# Octaverter_Rev_5.net
KiCad netlist of a schematic drawn in EAGLE
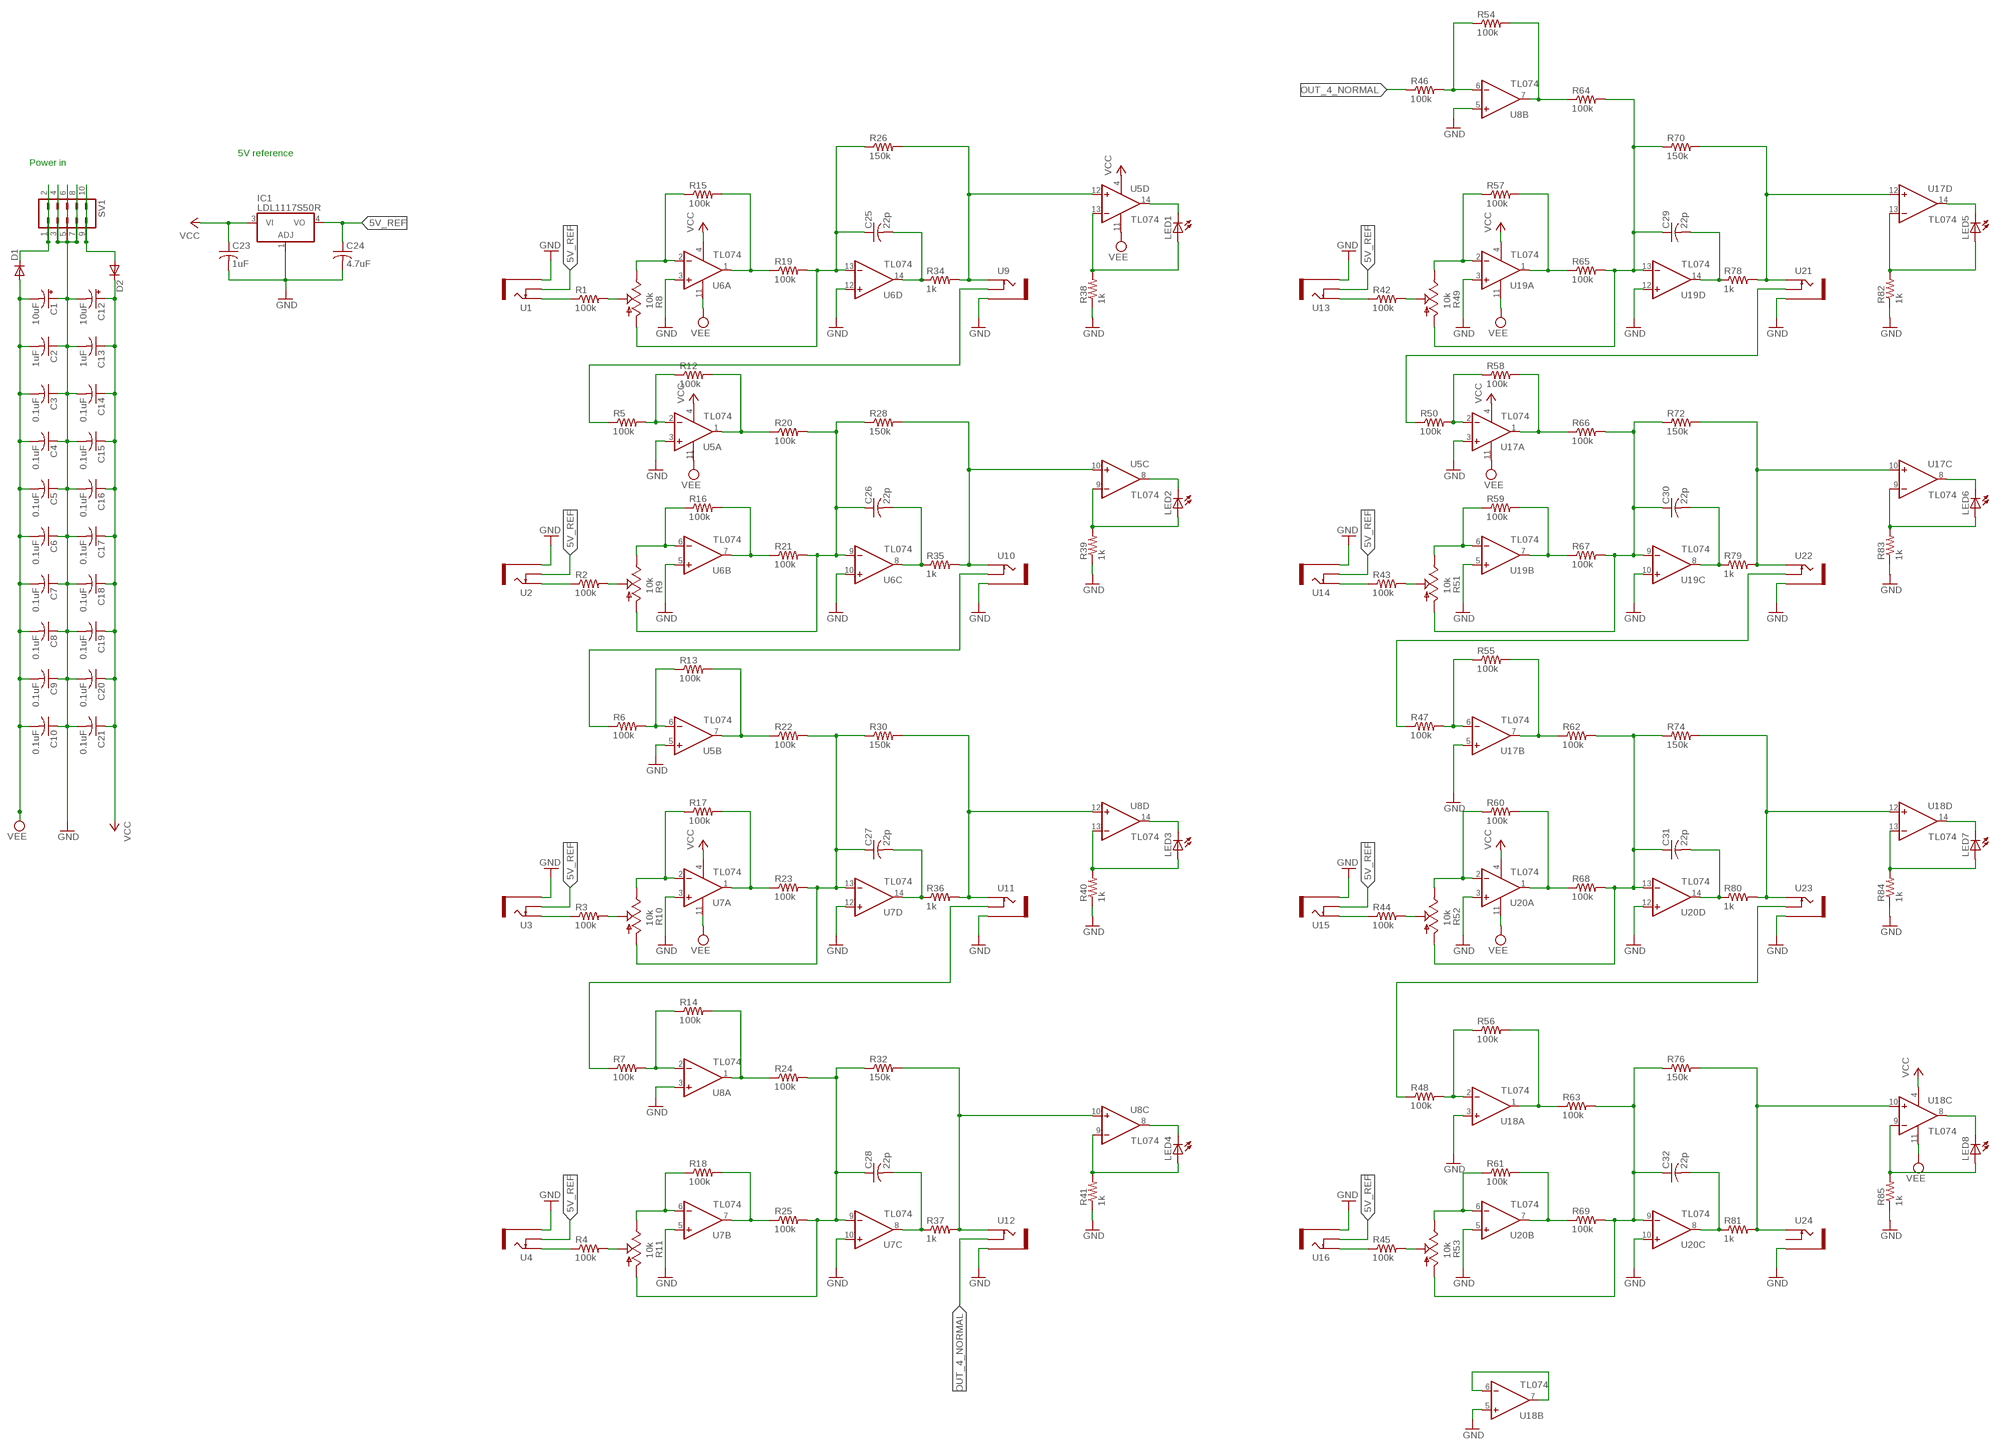
[diagram p0: schematic, sheet 1]

(export (version "E")
  (design (tool "Eeschema 10.0.6"))
  (components
    (comp (ref "C1")
      (value "10uF")
      (footprint "eagle-import:PANASONIC_B")
      (libsource (lib "eagle-import") (part "CPOL-USB"))
    )
    (comp (ref "C2")
      (value "1uF")
      (footprint "eagle-import:C0603")
      (libsource (lib "eagle-import") (part "C-USC0603"))
    )
    (comp (ref "C3")
      (value "0.1uF")
      (footprint "eagle-import:C0603")
      (libsource (lib "eagle-import") (part "C-USC0603"))
    )
    (comp (ref "C4")
      (value "0.1uF")
      (footprint "eagle-import:C0603")
      (libsource (lib "eagle-import") (part "C-USC0603"))
    )
    (comp (ref "C5")
      (value "0.1uF")
      (footprint "eagle-import:C0603")
      (libsource (lib "eagle-import") (part "C-USC0603"))
    )
    (comp (ref "C6")
      (value "0.1uF")
      (footprint "eagle-import:C0603")
      (libsource (lib "eagle-import") (part "C-USC0603"))
    )
    (comp (ref "C7")
      (value "0.1uF")
      (footprint "eagle-import:C0603")
      (libsource (lib "eagle-import") (part "C-USC0603"))
    )
    (comp (ref "C8")
      (value "0.1uF")
      (footprint "eagle-import:C0603")
      (libsource (lib "eagle-import") (part "C-USC0603"))
    )
    (comp (ref "C9")
      (value "0.1uF")
      (footprint "eagle-import:C0603")
      (libsource (lib "eagle-import") (part "C-USC0603"))
    )
    (comp (ref "C10")
      (value "0.1uF")
      (footprint "eagle-import:C0603")
      (libsource (lib "eagle-import") (part "C-USC0603"))
    )
    (comp (ref "C12")
      (value "10uF")
      (footprint "eagle-import:PANASONIC_B")
      (libsource (lib "eagle-import") (part "CPOL-USB"))
    )
    (comp (ref "C13")
      (value "1uF")
      (footprint "eagle-import:C0603")
      (libsource (lib "eagle-import") (part "C-USC0603"))
    )
    (comp (ref "C14")
      (value "0.1uF")
      (footprint "eagle-import:C0603")
      (libsource (lib "eagle-import") (part "C-USC0603"))
    )
    (comp (ref "C15")
      (value "0.1uF")
      (footprint "eagle-import:C0603")
      (libsource (lib "eagle-import") (part "C-USC0603"))
    )
    (comp (ref "C16")
      (value "0.1uF")
      (footprint "eagle-import:C0603")
      (libsource (lib "eagle-import") (part "C-USC0603"))
    )
    (comp (ref "C17")
      (value "0.1uF")
      (footprint "eagle-import:C0603")
      (libsource (lib "eagle-import") (part "C-USC0603"))
    )
    (comp (ref "C18")
      (value "0.1uF")
      (footprint "eagle-import:C0603")
      (libsource (lib "eagle-import") (part "C-USC0603"))
    )
    (comp (ref "C19")
      (value "0.1uF")
      (footprint "eagle-import:C0603")
      (libsource (lib "eagle-import") (part "C-USC0603"))
    )
    (comp (ref "C20")
      (value "0.1uF")
      (footprint "eagle-import:C0603")
      (libsource (lib "eagle-import") (part "C-USC0603"))
    )
    (comp (ref "C21")
      (value "0.1uF")
      (footprint "eagle-import:C0603")
      (libsource (lib "eagle-import") (part "C-USC0603"))
    )
    (comp (ref "C23")
      (value "1uF")
      (footprint "eagle-import:C0603")
      (libsource (lib "eagle-import") (part "C-USC0603"))
    )
    (comp (ref "C24")
      (value "4.7uF")
      (footprint "eagle-import:C0603")
      (libsource (lib "eagle-import") (part "C-USC0603"))
    )
    (comp (ref "C25")
      (value "22p")
      (footprint "eagle-import:C0603")
      (libsource (lib "eagle-import") (part "C-USC0603"))
    )
    (comp (ref "C26")
      (value "22p")
      (footprint "eagle-import:C0603")
      (libsource (lib "eagle-import") (part "C-USC0603"))
    )
    (comp (ref "C27")
      (value "22p")
      (footprint "eagle-import:C0603")
      (libsource (lib "eagle-import") (part "C-USC0603"))
    )
    (comp (ref "C28")
      (value "22p")
      (footprint "eagle-import:C0603")
      (libsource (lib "eagle-import") (part "C-USC0603"))
    )
    (comp (ref "C29")
      (value "22p")
      (footprint "eagle-import:C0603")
      (libsource (lib "eagle-import") (part "C-USC0603"))
    )
    (comp (ref "C30")
      (value "22p")
      (footprint "eagle-import:C0603")
      (libsource (lib "eagle-import") (part "C-USC0603"))
    )
    (comp (ref "C31")
      (value "22p")
      (footprint "eagle-import:C0603")
      (libsource (lib "eagle-import") (part "C-USC0603"))
    )
    (comp (ref "C32")
      (value "22p")
      (footprint "eagle-import:C0603")
      (libsource (lib "eagle-import") (part "C-USC0603"))
    )
    (comp (ref "D1")
      (value "1N5819HW")
      (footprint "eagle-import:SOD123")
      (libsource (lib "eagle-import") (part "DIODE-SOD123"))
    )
    (comp (ref "D2")
      (value "1N5819HW")
      (footprint "eagle-import:SOD123")
      (libsource (lib "eagle-import") (part "DIODE-SOD123"))
    )
    (comp (ref "IC1")
      (value "LDL1117S50R")
      (footprint "eagle-import:SOT223")
      (libsource (lib "eagle-import") (part "317EMP"))
    )
    (comp (ref "LED1")
      (value "LED3MM")
      (footprint "eagle-import:LED3MM")
      (libsource (lib "eagle-import") (part "LED3MM"))
    )
    (comp (ref "LED2")
      (value "LED3MM")
      (footprint "eagle-import:LED3MM")
      (libsource (lib "eagle-import") (part "LED3MM"))
    )
    (comp (ref "LED3")
      (value "LED3MM")
      (footprint "eagle-import:LED3MM")
      (libsource (lib "eagle-import") (part "LED3MM"))
    )
    (comp (ref "LED4")
      (value "LED3MM")
      (footprint "eagle-import:LED3MM")
      (libsource (lib "eagle-import") (part "LED3MM"))
    )
    (comp (ref "LED5")
      (value "LED3MM")
      (footprint "eagle-import:LED3MM")
      (libsource (lib "eagle-import") (part "LED3MM"))
    )
    (comp (ref "LED6")
      (value "LED3MM")
      (footprint "eagle-import:LED3MM")
      (libsource (lib "eagle-import") (part "LED3MM"))
    )
    (comp (ref "LED7")
      (value "LED3MM")
      (footprint "eagle-import:LED3MM")
      (libsource (lib "eagle-import") (part "LED3MM"))
    )
    (comp (ref "LED8")
      (value "LED3MM")
      (footprint "eagle-import:LED3MM")
      (libsource (lib "eagle-import") (part "LED3MM"))
    )
    (comp (ref "R1")
      (value "100k")
      (footprint "eagle-import:R0603")
      (libsource (lib "eagle-import") (part "R-US_R0603"))
    )
    (comp (ref "R2")
      (value "100k")
      (footprint "eagle-import:R0603")
      (libsource (lib "eagle-import") (part "R-US_R0603"))
    )
    (comp (ref "R3")
      (value "100k")
      (footprint "eagle-import:R0603")
      (libsource (lib "eagle-import") (part "R-US_R0603"))
    )
    (comp (ref "R4")
      (value "100k")
      (footprint "eagle-import:R0603")
      (libsource (lib "eagle-import") (part "R-US_R0603"))
    )
    (comp (ref "R5")
      (value "100k")
      (footprint "eagle-import:R0603")
      (libsource (lib "eagle-import") (part "R-US_R0603"))
    )
    (comp (ref "R6")
      (value "100k")
      (footprint "eagle-import:R0603")
      (libsource (lib "eagle-import") (part "R-US_R0603"))
    )
    (comp (ref "R7")
      (value "100k")
      (footprint "eagle-import:R0603")
      (libsource (lib "eagle-import") (part "R-US_R0603"))
    )
    (comp (ref "R8")
      (value "10k")
      (footprint "eagle-import:ALPS_POT_VERTICAL_PS")
      (libsource (lib "eagle-import") (part "POT_USVERTICAL_PS"))
    )
    (comp (ref "R9")
      (value "10k")
      (footprint "eagle-import:ALPS_POT_VERTICAL_PS")
      (libsource (lib "eagle-import") (part "POT_USVERTICAL_PS"))
    )
    (comp (ref "R10")
      (value "10k")
      (footprint "eagle-import:ALPS_POT_VERTICAL_PS")
      (libsource (lib "eagle-import") (part "POT_USVERTICAL_PS"))
    )
    (comp (ref "R11")
      (value "10k")
      (footprint "eagle-import:ALPS_POT_VERTICAL_PS")
      (libsource (lib "eagle-import") (part "POT_USVERTICAL_PS"))
    )
    (comp (ref "R12")
      (value "100k")
      (footprint "eagle-import:R0603")
      (libsource (lib "eagle-import") (part "R-US_R0603"))
    )
    (comp (ref "R13")
      (value "100k")
      (footprint "eagle-import:R0603")
      (libsource (lib "eagle-import") (part "R-US_R0603"))
    )
    (comp (ref "R14")
      (value "100k")
      (footprint "eagle-import:R0603")
      (libsource (lib "eagle-import") (part "R-US_R0603"))
    )
    (comp (ref "R15")
      (value "100k")
      (footprint "eagle-import:R0603")
      (libsource (lib "eagle-import") (part "R-US_R0603"))
    )
    (comp (ref "R16")
      (value "100k")
      (footprint "eagle-import:R0603")
      (libsource (lib "eagle-import") (part "R-US_R0603"))
    )
    (comp (ref "R17")
      (value "100k")
      (footprint "eagle-import:R0603")
      (libsource (lib "eagle-import") (part "R-US_R0603"))
    )
    (comp (ref "R18")
      (value "100k")
      (footprint "eagle-import:R0603")
      (libsource (lib "eagle-import") (part "R-US_R0603"))
    )
    (comp (ref "R19")
      (value "100k")
      (footprint "eagle-import:R0603")
      (libsource (lib "eagle-import") (part "R-US_R0603"))
    )
    (comp (ref "R20")
      (value "100k")
      (footprint "eagle-import:R0603")
      (libsource (lib "eagle-import") (part "R-US_R0603"))
    )
    (comp (ref "R21")
      (value "100k")
      (footprint "eagle-import:R0603")
      (libsource (lib "eagle-import") (part "R-US_R0603"))
    )
    (comp (ref "R22")
      (value "100k")
      (footprint "eagle-import:R0603")
      (libsource (lib "eagle-import") (part "R-US_R0603"))
    )
    (comp (ref "R23")
      (value "100k")
      (footprint "eagle-import:R0603")
      (libsource (lib "eagle-import") (part "R-US_R0603"))
    )
    (comp (ref "R24")
      (value "100k")
      (footprint "eagle-import:R0603")
      (libsource (lib "eagle-import") (part "R-US_R0603"))
    )
    (comp (ref "R25")
      (value "100k")
      (footprint "eagle-import:R0603")
      (libsource (lib "eagle-import") (part "R-US_R0603"))
    )
    (comp (ref "R26")
      (value "150k")
      (footprint "eagle-import:R0603")
      (libsource (lib "eagle-import") (part "R-US_R0603"))
    )
    (comp (ref "R28")
      (value "150k")
      (footprint "eagle-import:R0603")
      (libsource (lib "eagle-import") (part "R-US_R0603"))
    )
    (comp (ref "R30")
      (value "150k")
      (footprint "eagle-import:R0603")
      (libsource (lib "eagle-import") (part "R-US_R0603"))
    )
    (comp (ref "R32")
      (value "150k")
      (footprint "eagle-import:R0603")
      (libsource (lib "eagle-import") (part "R-US_R0603"))
    )
    (comp (ref "R34")
      (value "1k")
      (footprint "eagle-import:R0603")
      (libsource (lib "eagle-import") (part "R-US_R0603"))
    )
    (comp (ref "R35")
      (value "1k")
      (footprint "eagle-import:R0603")
      (libsource (lib "eagle-import") (part "R-US_R0603"))
    )
    (comp (ref "R36")
      (value "1k")
      (footprint "eagle-import:R0603")
      (libsource (lib "eagle-import") (part "R-US_R0603"))
    )
    (comp (ref "R37")
      (value "1k")
      (footprint "eagle-import:R0603")
      (libsource (lib "eagle-import") (part "R-US_R0603"))
    )
    (comp (ref "R38")
      (value "1k")
      (footprint "eagle-import:R0603")
      (libsource (lib "eagle-import") (part "R-US_R0603"))
    )
    (comp (ref "R39")
      (value "1k")
      (footprint "eagle-import:R0603")
      (libsource (lib "eagle-import") (part "R-US_R0603"))
    )
    (comp (ref "R40")
      (value "1k")
      (footprint "eagle-import:R0603")
      (libsource (lib "eagle-import") (part "R-US_R0603"))
    )
    (comp (ref "R41")
      (value "1k")
      (footprint "eagle-import:R0603")
      (libsource (lib "eagle-import") (part "R-US_R0603"))
    )
    (comp (ref "R42")
      (value "100k")
      (footprint "eagle-import:R0603")
      (libsource (lib "eagle-import") (part "R-US_R0603"))
    )
    (comp (ref "R43")
      (value "100k")
      (footprint "eagle-import:R0603")
      (libsource (lib "eagle-import") (part "R-US_R0603"))
    )
    (comp (ref "R44")
      (value "100k")
      (footprint "eagle-import:R0603")
      (libsource (lib "eagle-import") (part "R-US_R0603"))
    )
    (comp (ref "R45")
      (value "100k")
      (footprint "eagle-import:R0603")
      (libsource (lib "eagle-import") (part "R-US_R0603"))
    )
    (comp (ref "R46")
      (value "100k")
      (footprint "eagle-import:R0603")
      (libsource (lib "eagle-import") (part "R-US_R0603"))
    )
    (comp (ref "R47")
      (value "100k")
      (footprint "eagle-import:R0603")
      (libsource (lib "eagle-import") (part "R-US_R0603"))
    )
    (comp (ref "R48")
      (value "100k")
      (footprint "eagle-import:R0603")
      (libsource (lib "eagle-import") (part "R-US_R0603"))
    )
    (comp (ref "R49")
      (value "10k")
      (footprint "eagle-import:ALPS_POT_VERTICAL_PS")
      (libsource (lib "eagle-import") (part "POT_USVERTICAL_PS"))
    )
    (comp (ref "R50")
      (value "100k")
      (footprint "eagle-import:R0603")
      (libsource (lib "eagle-import") (part "R-US_R0603"))
    )
    (comp (ref "R51")
      (value "10k")
      (footprint "eagle-import:ALPS_POT_VERTICAL_PS")
      (libsource (lib "eagle-import") (part "POT_USVERTICAL_PS"))
    )
    (comp (ref "R52")
      (value "10k")
      (footprint "eagle-import:ALPS_POT_VERTICAL_PS")
      (libsource (lib "eagle-import") (part "POT_USVERTICAL_PS"))
    )
    (comp (ref "R53")
      (value "10k")
      (footprint "eagle-import:ALPS_POT_VERTICAL_PS")
      (libsource (lib "eagle-import") (part "POT_USVERTICAL_PS"))
    )
    (comp (ref "R54")
      (value "100k")
      (footprint "eagle-import:R0603")
      (libsource (lib "eagle-import") (part "R-US_R0603"))
    )
    (comp (ref "R55")
      (value "100k")
      (footprint "eagle-import:R0603")
      (libsource (lib "eagle-import") (part "R-US_R0603"))
    )
    (comp (ref "R56")
      (value "100k")
      (footprint "eagle-import:R0603")
      (libsource (lib "eagle-import") (part "R-US_R0603"))
    )
    (comp (ref "R57")
      (value "100k")
      (footprint "eagle-import:R0603")
      (libsource (lib "eagle-import") (part "R-US_R0603"))
    )
    (comp (ref "R58")
      (value "100k")
      (footprint "eagle-import:R0603")
      (libsource (lib "eagle-import") (part "R-US_R0603"))
    )
    (comp (ref "R59")
      (value "100k")
      (footprint "eagle-import:R0603")
      (libsource (lib "eagle-import") (part "R-US_R0603"))
    )
    (comp (ref "R60")
      (value "100k")
      (footprint "eagle-import:R0603")
      (libsource (lib "eagle-import") (part "R-US_R0603"))
    )
    (comp (ref "R61")
      (value "100k")
      (footprint "eagle-import:R0603")
      (libsource (lib "eagle-import") (part "R-US_R0603"))
    )
    (comp (ref "R62")
      (value "100k")
      (footprint "eagle-import:R0603")
      (libsource (lib "eagle-import") (part "R-US_R0603"))
    )
    (comp (ref "R63")
      (value "100k")
      (footprint "eagle-import:R0603")
      (libsource (lib "eagle-import") (part "R-US_R0603"))
    )
    (comp (ref "R64")
      (value "100k")
      (footprint "eagle-import:R0603")
      (libsource (lib "eagle-import") (part "R-US_R0603"))
    )
    (comp (ref "R65")
      (value "100k")
      (footprint "eagle-import:R0603")
      (libsource (lib "eagle-import") (part "R-US_R0603"))
    )
    (comp (ref "R66")
      (value "100k")
      (footprint "eagle-import:R0603")
      (libsource (lib "eagle-import") (part "R-US_R0603"))
    )
    (comp (ref "R67")
      (value "100k")
      (footprint "eagle-import:R0603")
      (libsource (lib "eagle-import") (part "R-US_R0603"))
    )
    (comp (ref "R68")
      (value "100k")
      (footprint "eagle-import:R0603")
      (libsource (lib "eagle-import") (part "R-US_R0603"))
    )
    (comp (ref "R69")
      (value "100k")
      (footprint "eagle-import:R0603")
      (libsource (lib "eagle-import") (part "R-US_R0603"))
    )
    (comp (ref "R70")
      (value "150k")
      (footprint "eagle-import:R0603")
      (libsource (lib "eagle-import") (part "R-US_R0603"))
    )
    (comp (ref "R72")
      (value "150k")
      (footprint "eagle-import:R0603")
      (libsource (lib "eagle-import") (part "R-US_R0603"))
    )
    (comp (ref "R74")
      (value "150k")
      (footprint "eagle-import:R0603")
      (libsource (lib "eagle-import") (part "R-US_R0603"))
    )
    (comp (ref "R76")
      (value "150k")
      (footprint "eagle-import:R0603")
      (libsource (lib "eagle-import") (part "R-US_R0603"))
    )
    (comp (ref "R78")
      (value "1k")
      (footprint "eagle-import:R0603")
      (libsource (lib "eagle-import") (part "R-US_R0603"))
    )
    (comp (ref "R79")
      (value "1k")
      (footprint "eagle-import:R0603")
      (libsource (lib "eagle-import") (part "R-US_R0603"))
    )
    (comp (ref "R80")
      (value "1k")
      (footprint "eagle-import:R0603")
      (libsource (lib "eagle-import") (part "R-US_R0603"))
    )
    (comp (ref "R81")
      (value "1k")
      (footprint "eagle-import:R0603")
      (libsource (lib "eagle-import") (part "R-US_R0603"))
    )
    (comp (ref "R82")
      (value "1k")
      (footprint "eagle-import:R0603")
      (libsource (lib "eagle-import") (part "R-US_R0603"))
    )
    (comp (ref "R83")
      (value "1k")
      (footprint "eagle-import:R0603")
      (libsource (lib "eagle-import") (part "R-US_R0603"))
    )
    (comp (ref "R84")
      (value "1k")
      (footprint "eagle-import:R0603")
      (libsource (lib "eagle-import") (part "R-US_R0603"))
    )
    (comp (ref "R85")
      (value "1k")
      (footprint "eagle-import:R0603")
      (libsource (lib "eagle-import") (part "R-US_R0603"))
    )
    (comp (ref "SV1")
      (value "EURO_POWER_HEADERFAT_PADS")
      (footprint "eagle-import:EURO_PWR_HEADER_FAT")
      (libsource (lib "eagle-import") (part "EURO_POWER_HEADERFAT_PADS"))
    )
    (comp (ref "U1")
      (value "THONKICONNNEW")
      (footprint "eagle-import:WQP-PJ301M-12_JACK")
      (libsource (lib "eagle-import") (part "THONKICONNNEW"))
    )
    (comp (ref "U2")
      (value "THONKICONNNEW")
      (footprint "eagle-import:WQP-PJ301M-12_JACK")
      (libsource (lib "eagle-import") (part "THONKICONNNEW"))
    )
    (comp (ref "U3")
      (value "THONKICONNNEW")
      (footprint "eagle-import:WQP-PJ301M-12_JACK")
      (libsource (lib "eagle-import") (part "THONKICONNNEW"))
    )
    (comp (ref "U4")
      (value "THONKICONNNEW")
      (footprint "eagle-import:WQP-PJ301M-12_JACK")
      (libsource (lib "eagle-import") (part "THONKICONNNEW"))
    )
    (comp (ref "U5")
      (value "TL074")
      (footprint "eagle-import:SO14")
      (libsource (lib "eagle-import") (part "TL074_SMD"))
    )
    (comp (ref "U6")
      (value "TL074")
      (footprint "eagle-import:SO14")
      (libsource (lib "eagle-import") (part "TL074_SMD"))
    )
    (comp (ref "U7")
      (value "TL074")
      (footprint "eagle-import:SO14")
      (libsource (lib "eagle-import") (part "TL074_SMD"))
    )
    (comp (ref "U8")
      (value "TL074")
      (footprint "eagle-import:SO14")
      (libsource (lib "eagle-import") (part "TL074_SMD"))
    )
    (comp (ref "U9")
      (value "THONKICONNNEW")
      (footprint "eagle-import:WQP-PJ301M-12_JACK")
      (libsource (lib "eagle-import") (part "THONKICONNNEW"))
    )
    (comp (ref "U10")
      (value "THONKICONNNEW")
      (footprint "eagle-import:WQP-PJ301M-12_JACK")
      (libsource (lib "eagle-import") (part "THONKICONNNEW"))
    )
    (comp (ref "U11")
      (value "THONKICONNNEW")
      (footprint "eagle-import:WQP-PJ301M-12_JACK")
      (libsource (lib "eagle-import") (part "THONKICONNNEW"))
    )
    (comp (ref "U12")
      (value "THONKICONNNEW")
      (footprint "eagle-import:WQP-PJ301M-12_JACK")
      (libsource (lib "eagle-import") (part "THONKICONNNEW"))
    )
    (comp (ref "U13")
      (value "THONKICONNNEW")
      (footprint "eagle-import:WQP-PJ301M-12_JACK")
      (libsource (lib "eagle-import") (part "THONKICONNNEW"))
    )
    (comp (ref "U14")
      (value "THONKICONNNEW")
      (footprint "eagle-import:WQP-PJ301M-12_JACK")
      (libsource (lib "eagle-import") (part "THONKICONNNEW"))
    )
    (comp (ref "U15")
      (value "THONKICONNNEW")
      (footprint "eagle-import:WQP-PJ301M-12_JACK")
      (libsource (lib "eagle-import") (part "THONKICONNNEW"))
    )
    (comp (ref "U16")
      (value "THONKICONNNEW")
      (footprint "eagle-import:WQP-PJ301M-12_JACK")
      (libsource (lib "eagle-import") (part "THONKICONNNEW"))
    )
    (comp (ref "U17")
      (value "TL074")
      (footprint "eagle-import:SO14")
      (libsource (lib "eagle-import") (part "TL074_SMD"))
    )
    (comp (ref "U18")
      (value "TL074")
      (footprint "eagle-import:SO14")
      (libsource (lib "eagle-import") (part "TL074_SMD"))
    )
    (comp (ref "U19")
      (value "TL074")
      (footprint "eagle-import:SO14")
      (libsource (lib "eagle-import") (part "TL074_SMD"))
    )
    (comp (ref "U20")
      (value "TL074")
      (footprint "eagle-import:SO14")
      (libsource (lib "eagle-import") (part "TL074_SMD"))
    )
    (comp (ref "U21")
      (value "THONKICONNNEW")
      (footprint "eagle-import:WQP-PJ301M-12_JACK")
      (libsource (lib "eagle-import") (part "THONKICONNNEW"))
    )
    (comp (ref "U22")
      (value "THONKICONNNEW")
      (footprint "eagle-import:WQP-PJ301M-12_JACK")
      (libsource (lib "eagle-import") (part "THONKICONNNEW"))
    )
    (comp (ref "U23")
      (value "THONKICONNNEW")
      (footprint "eagle-import:WQP-PJ301M-12_JACK")
      (libsource (lib "eagle-import") (part "THONKICONNNEW"))
    )
    (comp (ref "U24")
      (value "THONKICONNNEW")
      (footprint "eagle-import:WQP-PJ301M-12_JACK")
      (libsource (lib "eagle-import") (part "THONKICONNNEW"))
    )
  )
  (nets
    (net (code "1") (name "5V_REF") (class "Default")
      (node (ref "C24") (pin "1") (pinfunction "1_1") (pintype "passive"))
      (node (ref "IC1") (pin "4") (pinfunction "VO_4") (pintype "passive"))
      (node (ref "U1") (pin "P$2_SWITCH") (pinfunction "SWITCH_P$2_SWITCH") (pintype "passive"))
      (node (ref "U13") (pin "P$2_SWITCH") (pinfunction "SWITCH_P$2_SWITCH") (pintype "passive"))
      (node (ref "U14") (pin "P$2_SWITCH") (pinfunction "SWITCH_P$2_SWITCH") (pintype "passive"))
      (node (ref "U15") (pin "P$2_SWITCH") (pinfunction "SWITCH_P$2_SWITCH") (pintype "passive"))
      (node (ref "U16") (pin "P$2_SWITCH") (pinfunction "SWITCH_P$2_SWITCH") (pintype "passive"))
      (node (ref "U2") (pin "P$2_SWITCH") (pinfunction "SWITCH_P$2_SWITCH") (pintype "passive"))
      (node (ref "U3") (pin "P$2_SWITCH") (pinfunction "SWITCH_P$2_SWITCH") (pintype "passive"))
      (node (ref "U4") (pin "P$2_SWITCH") (pinfunction "SWITCH_P$2_SWITCH") (pintype "passive"))
    )
    (net (code "2") (name "GND") (class "Default")
      (node (ref "C1") (pin "+") (pinfunction "+_+") (pintype "passive"))
      (node (ref "C10") (pin "1") (pinfunction "1_1") (pintype "passive"))
      (node (ref "C12") (pin "-") (pinfunction "-_-") (pintype "passive"))
      (node (ref "C13") (pin "2") (pinfunction "2_2") (pintype "passive"))
      (node (ref "C14") (pin "2") (pinfunction "2_2") (pintype "passive"))
      (node (ref "C15") (pin "2") (pinfunction "2_2") (pintype "passive"))
      (node (ref "C16") (pin "2") (pinfunction "2_2") (pintype "passive"))
      (node (ref "C17") (pin "2") (pinfunction "2_2") (pintype "passive"))
      (node (ref "C18") (pin "2") (pinfunction "2_2") (pintype "passive"))
      (node (ref "C19") (pin "2") (pinfunction "2_2") (pintype "passive"))
      (node (ref "C2") (pin "1") (pinfunction "1_1") (pintype "passive"))
      (node (ref "C20") (pin "2") (pinfunction "2_2") (pintype "passive"))
      (node (ref "C21") (pin "2") (pinfunction "2_2") (pintype "passive"))
      (node (ref "C23") (pin "2") (pinfunction "2_2") (pintype "passive"))
      (node (ref "C24") (pin "2") (pinfunction "2_2") (pintype "passive"))
      (node (ref "C3") (pin "1") (pinfunction "1_1") (pintype "passive"))
      (node (ref "C4") (pin "1") (pinfunction "1_1") (pintype "passive"))
      (node (ref "C5") (pin "1") (pinfunction "1_1") (pintype "passive"))
      (node (ref "C6") (pin "1") (pinfunction "1_1") (pintype "passive"))
      (node (ref "C7") (pin "1") (pinfunction "1_1") (pintype "passive"))
      (node (ref "C8") (pin "1") (pinfunction "1_1") (pintype "passive"))
      (node (ref "C9") (pin "1") (pinfunction "1_1") (pintype "passive"))
      (node (ref "IC1") (pin "1") (pinfunction "ADJ_1") (pintype "input"))
      (node (ref "R38") (pin "1") (pinfunction "1_1") (pintype "passive"))
      (node (ref "R39") (pin "1") (pinfunction "1_1") (pintype "passive"))
      (node (ref "R40") (pin "1") (pinfunction "1_1") (pintype "passive"))
      (node (ref "R41") (pin "1") (pinfunction "1_1") (pintype "passive"))
      (node (ref "R82") (pin "1") (pinfunction "1_1") (pintype "passive"))
      (node (ref "R83") (pin "1") (pinfunction "1_1") (pintype "passive"))
      (node (ref "R84") (pin "1") (pinfunction "1_1") (pintype "passive"))
      (node (ref "R85") (pin "1") (pinfunction "1_1") (pintype "passive"))
      (node (ref "SV1") (pin "3") (pinfunction "3_3") (pintype "passive"))
      (node (ref "SV1") (pin "4") (pinfunction "4_4") (pintype "passive"))
      (node (ref "SV1") (pin "5") (pinfunction "5_5") (pintype "passive"))
      (node (ref "SV1") (pin "6") (pinfunction "6_6") (pintype "passive"))
      (node (ref "SV1") (pin "7") (pinfunction "7_7") (pintype "passive"))
      (node (ref "SV1") (pin "8") (pinfunction "8_8") (pintype "passive"))
      (node (ref "U1") (pin "P$3_SLEEVE") (pinfunction "SLEEVE_P$3_SLEEVE") (pintype "passive"))
      (node (ref "U10") (pin "P$3_SLEEVE") (pinfunction "SLEEVE_P$3_SLEEVE") (pintype "passive"))
      (node (ref "U11") (pin "P$3_SLEEVE") (pinfunction "SLEEVE_P$3_SLEEVE") (pintype "passive"))
      (node (ref "U12") (pin "P$3_SLEEVE") (pinfunction "SLEEVE_P$3_SLEEVE") (pintype "passive"))
      (node (ref "U13") (pin "P$3_SLEEVE") (pinfunction "SLEEVE_P$3_SLEEVE") (pintype "passive"))
      (node (ref "U14") (pin "P$3_SLEEVE") (pinfunction "SLEEVE_P$3_SLEEVE") (pintype "passive"))
      (node (ref "U15") (pin "P$3_SLEEVE") (pinfunction "SLEEVE_P$3_SLEEVE") (pintype "passive"))
      (node (ref "U16") (pin "P$3_SLEEVE") (pinfunction "SLEEVE_P$3_SLEEVE") (pintype "passive"))
      (node (ref "U17") (pin "3") (pinfunction "+IN_3") (pintype "input"))
      (node (ref "U17") (pin "5") (pinfunction "+IN_5") (pintype "input"))
      (node (ref "U18") (pin "3") (pinfunction "+IN_3") (pintype "input"))
      (node (ref "U18") (pin "5") (pinfunction "+IN_5") (pintype "input"))
      (node (ref "U19") (pin "10") (pinfunction "+IN_10") (pintype "input"))
      (node (ref "U19") (pin "12") (pinfunction "+IN_12") (pintype "input"))
      (node (ref "U19") (pin "3") (pinfunction "+IN_3") (pintype "input"))
      (node (ref "U19") (pin "5") (pinfunction "+IN_5") (pintype "input"))
      (node (ref "U2") (pin "P$3_SLEEVE") (pinfunction "SLEEVE_P$3_SLEEVE") (pintype "passive"))
      (node (ref "U20") (pin "10") (pinfunction "+IN_10") (pintype "input"))
      (node (ref "U20") (pin "12") (pinfunction "+IN_12") (pintype "input"))
      (node (ref "U20") (pin "3") (pinfunction "+IN_3") (pintype "input"))
      (node (ref "U20") (pin "5") (pinfunction "+IN_5") (pintype "input"))
      (node (ref "U21") (pin "P$3_SLEEVE") (pinfunction "SLEEVE_P$3_SLEEVE") (pintype "passive"))
      (node (ref "U22") (pin "P$3_SLEEVE") (pinfunction "SLEEVE_P$3_SLEEVE") (pintype "passive"))
      (node (ref "U23") (pin "P$3_SLEEVE") (pinfunction "SLEEVE_P$3_SLEEVE") (pintype "passive"))
      (node (ref "U24") (pin "P$3_SLEEVE") (pinfunction "SLEEVE_P$3_SLEEVE") (pintype "passive"))
      (node (ref "U3") (pin "P$3_SLEEVE") (pinfunction "SLEEVE_P$3_SLEEVE") (pintype "passive"))
      (node (ref "U4") (pin "P$3_SLEEVE") (pinfunction "SLEEVE_P$3_SLEEVE") (pintype "passive"))
      (node (ref "U5") (pin "3") (pinfunction "+IN_3") (pintype "input"))
      (node (ref "U5") (pin "5") (pinfunction "+IN_5") (pintype "input"))
      (node (ref "U6") (pin "10") (pinfunction "+IN_10") (pintype "input"))
      (node (ref "U6") (pin "12") (pinfunction "+IN_12") (pintype "input"))
      (node (ref "U6") (pin "3") (pinfunction "+IN_3") (pintype "input"))
      (node (ref "U6") (pin "5") (pinfunction "+IN_5") (pintype "input"))
      (node (ref "U7") (pin "10") (pinfunction "+IN_10") (pintype "input"))
      (node (ref "U7") (pin "12") (pinfunction "+IN_12") (pintype "input"))
      (node (ref "U7") (pin "3") (pinfunction "+IN_3") (pintype "input"))
      (node (ref "U7") (pin "5") (pinfunction "+IN_5") (pintype "input"))
      (node (ref "U8") (pin "3") (pinfunction "+IN_3") (pintype "input"))
      (node (ref "U8") (pin "5") (pinfunction "+IN_5") (pintype "input"))
      (node (ref "U9") (pin "P$3_SLEEVE") (pinfunction "SLEEVE_P$3_SLEEVE") (pintype "passive"))
    )
    (net (code "3") (name "Net-(D1-PadC)") (class "Default")
      (node (ref "D1") (pin "C") (pinfunction "C_C") (pintype "passive"))
      (node (ref "SV1") (pin "1") (pinfunction "1_1") (pintype "passive"))
      (node (ref "SV1") (pin "2") (pinfunction "2_2") (pintype "passive"))
    )
    (net (code "4") (name "Net-(D2-PadA)") (class "Default")
      (node (ref "D2") (pin "A") (pinfunction "A_A") (pintype "passive"))
      (node (ref "SV1") (pin "10") (pinfunction "10_10") (pintype "passive"))
      (node (ref "SV1") (pin "9") (pinfunction "9_9") (pintype "passive"))
    )
    (net (code "5") (name "Net-(LED1-C)") (class "Default")
      (node (ref "LED1") (pin "K") (pinfunction "C_K") (pintype "passive"))
      (node (ref "U5") (pin "14") (pinfunction "OUT_14") (pintype "output"))
    )
    (net (code "6") (name "Net-(LED2-C)") (class "Default")
      (node (ref "LED2") (pin "K") (pinfunction "C_K") (pintype "passive"))
      (node (ref "U5") (pin "8") (pinfunction "OUT_8") (pintype "output"))
    )
    (net (code "7") (name "Net-(LED3-C)") (class "Default")
      (node (ref "LED3") (pin "K") (pinfunction "C_K") (pintype "passive"))
      (node (ref "U8") (pin "14") (pinfunction "OUT_14") (pintype "output"))
    )
    (net (code "8") (name "Net-(LED4-C)") (class "Default")
      (node (ref "LED4") (pin "K") (pinfunction "C_K") (pintype "passive"))
      (node (ref "U8") (pin "8") (pinfunction "OUT_8") (pintype "output"))
    )
    (net (code "9") (name "Net-(LED5-C)") (class "Default")
      (node (ref "LED5") (pin "K") (pinfunction "C_K") (pintype "passive"))
      (node (ref "U17") (pin "14") (pinfunction "OUT_14") (pintype "output"))
    )
    (net (code "10") (name "Net-(LED6-C)") (class "Default")
      (node (ref "LED6") (pin "K") (pinfunction "C_K") (pintype "passive"))
      (node (ref "U17") (pin "8") (pinfunction "OUT_8") (pintype "output"))
    )
    (net (code "11") (name "Net-(LED7-C)") (class "Default")
      (node (ref "LED7") (pin "K") (pinfunction "C_K") (pintype "passive"))
      (node (ref "U18") (pin "14") (pinfunction "OUT_14") (pintype "output"))
    )
    (net (code "12") (name "Net-(LED8-C)") (class "Default")
      (node (ref "LED8") (pin "K") (pinfunction "C_K") (pintype "passive"))
      (node (ref "U18") (pin "8") (pinfunction "OUT_8") (pintype "output"))
    )
    (net (code "13") (name "Net-(R8-A)") (class "Default")
      (node (ref "C25") (pin "1") (pinfunction "1_1") (pintype "passive"))
      (node (ref "R19") (pin "2") (pinfunction "2_2") (pintype "passive"))
      (node (ref "R26") (pin "1") (pinfunction "1_1") (pintype "passive"))
      (node (ref "R8") (pin "P$3") (pinfunction "A_P$3") (pintype "passive"))
      (node (ref "U6") (pin "13") (pinfunction "-IN_13") (pintype "input"))
    )
    (net (code "14") (name "Net-(R8-E)") (class "Default")
      (node (ref "R15") (pin "1") (pinfunction "1_1") (pintype "passive"))
      (node (ref "R8") (pin "P$1") (pinfunction "E_P$1") (pintype "passive"))
      (node (ref "U6") (pin "2") (pinfunction "-IN_2") (pintype "input"))
    )
    (net (code "15") (name "Net-(R8-S)") (class "Default")
      (node (ref "R1") (pin "2") (pinfunction "2_2") (pintype "passive"))
      (node (ref "R8") (pin "P$2") (pinfunction "S_P$2") (pintype "passive"))
    )
    (net (code "16") (name "Net-(R9-A)") (class "Default")
      (node (ref "C26") (pin "1") (pinfunction "1_1") (pintype "passive"))
      (node (ref "R20") (pin "2") (pinfunction "2_2") (pintype "passive"))
      (node (ref "R21") (pin "2") (pinfunction "2_2") (pintype "passive"))
      (node (ref "R28") (pin "1") (pinfunction "1_1") (pintype "passive"))
      (node (ref "R9") (pin "P$3") (pinfunction "A_P$3") (pintype "passive"))
      (node (ref "U6") (pin "9") (pinfunction "-IN_9") (pintype "input"))
    )
    (net (code "17") (name "Net-(R9-E)") (class "Default")
      (node (ref "R16") (pin "1") (pinfunction "1_1") (pintype "passive"))
      (node (ref "R9") (pin "P$1") (pinfunction "E_P$1") (pintype "passive"))
      (node (ref "U6") (pin "6") (pinfunction "-IN_6") (pintype "input"))
    )
    (net (code "18") (name "Net-(R9-S)") (class "Default")
      (node (ref "R2") (pin "2") (pinfunction "2_2") (pintype "passive"))
      (node (ref "R9") (pin "P$2") (pinfunction "S_P$2") (pintype "passive"))
    )
    (net (code "19") (name "Net-(R10-A)") (class "Default")
      (node (ref "C27") (pin "1") (pinfunction "1_1") (pintype "passive"))
      (node (ref "R10") (pin "P$3") (pinfunction "A_P$3") (pintype "passive"))
      (node (ref "R22") (pin "2") (pinfunction "2_2") (pintype "passive"))
      (node (ref "R23") (pin "2") (pinfunction "2_2") (pintype "passive"))
      (node (ref "R30") (pin "1") (pinfunction "1_1") (pintype "passive"))
      (node (ref "U7") (pin "13") (pinfunction "-IN_13") (pintype "input"))
    )
    (net (code "20") (name "Net-(R10-E)") (class "Default")
      (node (ref "R10") (pin "P$1") (pinfunction "E_P$1") (pintype "passive"))
      (node (ref "R17") (pin "1") (pinfunction "1_1") (pintype "passive"))
      (node (ref "U7") (pin "2") (pinfunction "-IN_2") (pintype "input"))
    )
    (net (code "21") (name "Net-(R10-S)") (class "Default")
      (node (ref "R10") (pin "P$2") (pinfunction "S_P$2") (pintype "passive"))
      (node (ref "R3") (pin "2") (pinfunction "2_2") (pintype "passive"))
    )
    (net (code "22") (name "Net-(R11-A)") (class "Default")
      (node (ref "C28") (pin "1") (pinfunction "1_1") (pintype "passive"))
      (node (ref "R11") (pin "P$3") (pinfunction "A_P$3") (pintype "passive"))
      (node (ref "R24") (pin "2") (pinfunction "2_2") (pintype "passive"))
      (node (ref "R25") (pin "2") (pinfunction "2_2") (pintype "passive"))
      (node (ref "R32") (pin "1") (pinfunction "1_1") (pintype "passive"))
      (node (ref "U7") (pin "9") (pinfunction "-IN_9") (pintype "input"))
    )
    (net (code "23") (name "Net-(R11-E)") (class "Default")
      (node (ref "R11") (pin "P$1") (pinfunction "E_P$1") (pintype "passive"))
      (node (ref "R18") (pin "1") (pinfunction "1_1") (pintype "passive"))
      (node (ref "U7") (pin "6") (pinfunction "-IN_6") (pintype "input"))
    )
    (net (code "24") (name "Net-(R11-S)") (class "Default")
      (node (ref "R11") (pin "P$2") (pinfunction "S_P$2") (pintype "passive"))
      (node (ref "R4") (pin "2") (pinfunction "2_2") (pintype "passive"))
    )
    (net (code "25") (name "Net-(R49-A)") (class "Default")
      (node (ref "C29") (pin "1") (pinfunction "1_1") (pintype "passive"))
      (node (ref "R49") (pin "P$3") (pinfunction "A_P$3") (pintype "passive"))
      (node (ref "R64") (pin "2") (pinfunction "2_2") (pintype "passive"))
      (node (ref "R65") (pin "2") (pinfunction "2_2") (pintype "passive"))
      (node (ref "R70") (pin "1") (pinfunction "1_1") (pintype "passive"))
      (node (ref "U19") (pin "13") (pinfunction "-IN_13") (pintype "input"))
    )
    (net (code "26") (name "Net-(R49-E)") (class "Default")
      (node (ref "R49") (pin "P$1") (pinfunction "E_P$1") (pintype "passive"))
      (node (ref "R57") (pin "1") (pinfunction "1_1") (pintype "passive"))
      (node (ref "U19") (pin "2") (pinfunction "-IN_2") (pintype "input"))
    )
    (net (code "27") (name "Net-(R49-S)") (class "Default")
      (node (ref "R42") (pin "2") (pinfunction "2_2") (pintype "passive"))
      (node (ref "R49") (pin "P$2") (pinfunction "S_P$2") (pintype "passive"))
    )
    (net (code "28") (name "Net-(R51-A)") (class "Default")
      (node (ref "C30") (pin "1") (pinfunction "1_1") (pintype "passive"))
      (node (ref "R51") (pin "P$3") (pinfunction "A_P$3") (pintype "passive"))
      (node (ref "R66") (pin "2") (pinfunction "2_2") (pintype "passive"))
      (node (ref "R67") (pin "2") (pinfunction "2_2") (pintype "passive"))
      (node (ref "R72") (pin "1") (pinfunction "1_1") (pintype "passive"))
      (node (ref "U19") (pin "9") (pinfunction "-IN_9") (pintype "input"))
    )
    (net (code "29") (name "Net-(R51-E)") (class "Default")
      (node (ref "R51") (pin "P$1") (pinfunction "E_P$1") (pintype "passive"))
      (node (ref "R59") (pin "1") (pinfunction "1_1") (pintype "passive"))
      (node (ref "U19") (pin "6") (pinfunction "-IN_6") (pintype "input"))
    )
    (net (code "30") (name "Net-(R51-S)") (class "Default")
      (node (ref "R43") (pin "2") (pinfunction "2_2") (pintype "passive"))
      (node (ref "R51") (pin "P$2") (pinfunction "S_P$2") (pintype "passive"))
    )
    (net (code "31") (name "Net-(R52-A)") (class "Default")
      (node (ref "C31") (pin "1") (pinfunction "1_1") (pintype "passive"))
      (node (ref "R52") (pin "P$3") (pinfunction "A_P$3") (pintype "passive"))
      (node (ref "R62") (pin "2") (pinfunction "2_2") (pintype "passive"))
      (node (ref "R68") (pin "2") (pinfunction "2_2") (pintype "passive"))
      (node (ref "R74") (pin "1") (pinfunction "1_1") (pintype "passive"))
      (node (ref "U20") (pin "13") (pinfunction "-IN_13") (pintype "input"))
    )
    (net (code "32") (name "Net-(R52-E)") (class "Default")
      (node (ref "R52") (pin "P$1") (pinfunction "E_P$1") (pintype "passive"))
      (node (ref "R60") (pin "1") (pinfunction "1_1") (pintype "passive"))
      (node (ref "U20") (pin "2") (pinfunction "-IN_2") (pintype "input"))
    )
    (net (code "33") (name "Net-(R52-S)") (class "Default")
      (node (ref "R44") (pin "2") (pinfunction "2_2") (pintype "passive"))
      (node (ref "R52") (pin "P$2") (pinfunction "S_P$2") (pintype "passive"))
    )
    (net (code "34") (name "Net-(R53-A)") (class "Default")
      (node (ref "C32") (pin "1") (pinfunction "1_1") (pintype "passive"))
      (node (ref "R53") (pin "P$3") (pinfunction "A_P$3") (pintype "passive"))
      (node (ref "R63") (pin "2") (pinfunction "2_2") (pintype "passive"))
      (node (ref "R69") (pin "2") (pinfunction "2_2") (pintype "passive"))
      (node (ref "R76") (pin "1") (pinfunction "1_1") (pintype "passive"))
      (node (ref "U20") (pin "9") (pinfunction "-IN_9") (pintype "input"))
    )
    (net (code "35") (name "Net-(R53-E)") (class "Default")
      (node (ref "R53") (pin "P$1") (pinfunction "E_P$1") (pintype "passive"))
      (node (ref "R61") (pin "1") (pinfunction "1_1") (pintype "passive"))
      (node (ref "U20") (pin "6") (pinfunction "-IN_6") (pintype "input"))
    )
    (net (code "36") (name "Net-(R53-S)") (class "Default")
      (node (ref "R45") (pin "2") (pinfunction "2_2") (pintype "passive"))
      (node (ref "R53") (pin "P$2") (pinfunction "S_P$2") (pintype "passive"))
    )
    (net (code "37") (name "Net-(U1-TIP)") (class "Default")
      (node (ref "R1") (pin "1") (pinfunction "1_1") (pintype "passive"))
      (node (ref "U1") (pin "P$1_TIP") (pinfunction "TIP_P$1_TIP") (pintype "passive"))
    )
    (net (code "38") (name "Net-(U2-TIP)") (class "Default")
      (node (ref "R2") (pin "1") (pinfunction "1_1") (pintype "passive"))
      (node (ref "U2") (pin "P$1_TIP") (pinfunction "TIP_P$1_TIP") (pintype "passive"))
    )
    (net (code "39") (name "Net-(U3-TIP)") (class "Default")
      (node (ref "R3") (pin "1") (pinfunction "1_1") (pintype "passive"))
      (node (ref "U3") (pin "P$1_TIP") (pinfunction "TIP_P$1_TIP") (pintype "passive"))
    )
    (net (code "40") (name "Net-(U4-TIP)") (class "Default")
      (node (ref "R4") (pin "1") (pinfunction "1_1") (pintype "passive"))
      (node (ref "U4") (pin "P$1_TIP") (pinfunction "TIP_P$1_TIP") (pintype "passive"))
    )
    (net (code "41") (name "Net-(U5A--IN)") (class "Default")
      (node (ref "R12") (pin "1") (pinfunction "1_1") (pintype "passive"))
      (node (ref "R5") (pin "2") (pinfunction "2_2") (pintype "passive"))
      (node (ref "U5") (pin "2") (pinfunction "-IN_2") (pintype "input"))
    )
    (net (code "42") (name "Net-(U5A-OUT)") (class "Default")
      (node (ref "R12") (pin "2") (pinfunction "2_2") (pintype "passive"))
      (node (ref "R20") (pin "1") (pinfunction "1_1") (pintype "passive"))
      (node (ref "U5") (pin "1") (pinfunction "OUT_1") (pintype "output"))
    )
    (net (code "43") (name "Net-(U5B--IN)") (class "Default")
      (node (ref "R13") (pin "1") (pinfunction "1_1") (pintype "passive"))
      (node (ref "R6") (pin "2") (pinfunction "2_2") (pintype "passive"))
      (node (ref "U5") (pin "6") (pinfunction "-IN_6") (pintype "input"))
    )
    (net (code "44") (name "Net-(U5B-OUT)") (class "Default")
      (node (ref "R13") (pin "2") (pinfunction "2_2") (pintype "passive"))
      (node (ref "R22") (pin "1") (pinfunction "1_1") (pintype "passive"))
      (node (ref "U5") (pin "7") (pinfunction "OUT_7") (pintype "output"))
    )
    (net (code "45") (name "Net-(U5C--IN)") (class "Default")
      (node (ref "LED2") (pin "A") (pinfunction "A_A") (pintype "passive"))
      (node (ref "R39") (pin "2") (pinfunction "2_2") (pintype "passive"))
      (node (ref "U5") (pin "9") (pinfunction "-IN_9") (pintype "input"))
    )
    (net (code "46") (name "Net-(U5D-+IN)") (class "Default")
      (node (ref "R26") (pin "2") (pinfunction "2_2") (pintype "passive"))
      (node (ref "R34") (pin "2") (pinfunction "2_2") (pintype "passive"))
      (node (ref "U5") (pin "12") (pinfunction "+IN_12") (pintype "input"))
      (node (ref "U9") (pin "P$1_TIP") (pinfunction "TIP_P$1_TIP") (pintype "passive"))
    )
    (net (code "47") (name "Net-(U5D--IN)") (class "Default")
      (node (ref "LED1") (pin "A") (pinfunction "A_A") (pintype "passive"))
      (node (ref "R38") (pin "2") (pinfunction "2_2") (pintype "passive"))
      (node (ref "U5") (pin "13") (pinfunction "-IN_13") (pintype "input"))
    )
    (net (code "48") (name "Net-(U6A-OUT)") (class "Default")
      (node (ref "R15") (pin "2") (pinfunction "2_2") (pintype "passive"))
      (node (ref "R19") (pin "1") (pinfunction "1_1") (pintype "passive"))
      (node (ref "U6") (pin "1") (pinfunction "OUT_1") (pintype "output"))
    )
    (net (code "49") (name "Net-(U6B-OUT)") (class "Default")
      (node (ref "R16") (pin "2") (pinfunction "2_2") (pintype "passive"))
      (node (ref "R21") (pin "1") (pinfunction "1_1") (pintype "passive"))
      (node (ref "U6") (pin "7") (pinfunction "OUT_7") (pintype "output"))
    )
    (net (code "50") (name "Net-(U6C-OUT)") (class "Default")
      (node (ref "C26") (pin "2") (pinfunction "2_2") (pintype "passive"))
      (node (ref "R35") (pin "1") (pinfunction "1_1") (pintype "passive"))
      (node (ref "U6") (pin "8") (pinfunction "OUT_8") (pintype "output"))
    )
    (net (code "51") (name "Net-(U6D-OUT)") (class "Default")
      (node (ref "C25") (pin "2") (pinfunction "2_2") (pintype "passive"))
      (node (ref "R34") (pin "1") (pinfunction "1_1") (pintype "passive"))
      (node (ref "U6") (pin "14") (pinfunction "OUT_14") (pintype "output"))
    )
    (net (code "52") (name "Net-(U7A-OUT)") (class "Default")
      (node (ref "R17") (pin "2") (pinfunction "2_2") (pintype "passive"))
      (node (ref "R23") (pin "1") (pinfunction "1_1") (pintype "passive"))
      (node (ref "U7") (pin "1") (pinfunction "OUT_1") (pintype "output"))
    )
    (net (code "53") (name "Net-(U7B-OUT)") (class "Default")
      (node (ref "R18") (pin "2") (pinfunction "2_2") (pintype "passive"))
      (node (ref "R25") (pin "1") (pinfunction "1_1") (pintype "passive"))
      (node (ref "U7") (pin "7") (pinfunction "OUT_7") (pintype "output"))
    )
    (net (code "54") (name "Net-(U7C-OUT)") (class "Default")
      (node (ref "C28") (pin "2") (pinfunction "2_2") (pintype "passive"))
      (node (ref "R37") (pin "1") (pinfunction "1_1") (pintype "passive"))
      (node (ref "U7") (pin "8") (pinfunction "OUT_8") (pintype "output"))
    )
    (net (code "55") (name "Net-(U7D-OUT)") (class "Default")
      (node (ref "C27") (pin "2") (pinfunction "2_2") (pintype "passive"))
      (node (ref "R36") (pin "1") (pinfunction "1_1") (pintype "passive"))
      (node (ref "U7") (pin "14") (pinfunction "OUT_14") (pintype "output"))
    )
    (net (code "56") (name "Net-(U8A--IN)") (class "Default")
      (node (ref "R14") (pin "1") (pinfunction "1_1") (pintype "passive"))
      (node (ref "R7") (pin "2") (pinfunction "2_2") (pintype "passive"))
      (node (ref "U8") (pin "2") (pinfunction "-IN_2") (pintype "input"))
    )
    (net (code "57") (name "Net-(U8A-OUT)") (class "Default")
      (node (ref "R14") (pin "2") (pinfunction "2_2") (pintype "passive"))
      (node (ref "R24") (pin "1") (pinfunction "1_1") (pintype "passive"))
      (node (ref "U8") (pin "1") (pinfunction "OUT_1") (pintype "output"))
    )
    (net (code "58") (name "Net-(U8B--IN)") (class "Default")
      (node (ref "R46") (pin "2") (pinfunction "2_2") (pintype "passive"))
      (node (ref "R54") (pin "1") (pinfunction "1_1") (pintype "passive"))
      (node (ref "U8") (pin "6") (pinfunction "-IN_6") (pintype "input"))
    )
    (net (code "59") (name "Net-(U8B-OUT)") (class "Default")
      (node (ref "R54") (pin "2") (pinfunction "2_2") (pintype "passive"))
      (node (ref "R64") (pin "1") (pinfunction "1_1") (pintype "passive"))
      (node (ref "U8") (pin "7") (pinfunction "OUT_7") (pintype "output"))
    )
    (net (code "60") (name "Net-(U8C--IN)") (class "Default")
      (node (ref "LED4") (pin "A") (pinfunction "A_A") (pintype "passive"))
      (node (ref "R41") (pin "2") (pinfunction "2_2") (pintype "passive"))
      (node (ref "U8") (pin "9") (pinfunction "-IN_9") (pintype "input"))
    )
    (net (code "61") (name "Net-(U8D--IN)") (class "Default")
      (node (ref "LED3") (pin "A") (pinfunction "A_A") (pintype "passive"))
      (node (ref "R40") (pin "2") (pinfunction "2_2") (pintype "passive"))
      (node (ref "U8") (pin "13") (pinfunction "-IN_13") (pintype "input"))
    )
    (net (code "62") (name "Net-(U9-SWITCH)") (class "Default")
      (node (ref "R5") (pin "1") (pinfunction "1_1") (pintype "passive"))
      (node (ref "U9") (pin "P$2_SWITCH") (pinfunction "SWITCH_P$2_SWITCH") (pintype "passive"))
    )
    (net (code "63") (name "Net-(U10-SWITCH)") (class "Default")
      (node (ref "R6") (pin "1") (pinfunction "1_1") (pintype "passive"))
      (node (ref "U10") (pin "P$2_SWITCH") (pinfunction "SWITCH_P$2_SWITCH") (pintype "passive"))
    )
    (net (code "64") (name "Net-(U10-TIP)") (class "Default")
      (node (ref "R28") (pin "2") (pinfunction "2_2") (pintype "passive"))
      (node (ref "R35") (pin "2") (pinfunction "2_2") (pintype "passive"))
      (node (ref "U10") (pin "P$1_TIP") (pinfunction "TIP_P$1_TIP") (pintype "passive"))
      (node (ref "U5") (pin "10") (pinfunction "+IN_10") (pintype "input"))
    )
    (net (code "65") (name "Net-(U11-SWITCH)") (class "Default")
      (node (ref "R7") (pin "1") (pinfunction "1_1") (pintype "passive"))
      (node (ref "U11") (pin "P$2_SWITCH") (pinfunction "SWITCH_P$2_SWITCH") (pintype "passive"))
    )
    (net (code "66") (name "Net-(U11-TIP)") (class "Default")
      (node (ref "R30") (pin "2") (pinfunction "2_2") (pintype "passive"))
      (node (ref "R36") (pin "2") (pinfunction "2_2") (pintype "passive"))
      (node (ref "U11") (pin "P$1_TIP") (pinfunction "TIP_P$1_TIP") (pintype "passive"))
      (node (ref "U8") (pin "12") (pinfunction "+IN_12") (pintype "input"))
    )
    (net (code "67") (name "Net-(U12-TIP)") (class "Default")
      (node (ref "R32") (pin "2") (pinfunction "2_2") (pintype "passive"))
      (node (ref "R37") (pin "2") (pinfunction "2_2") (pintype "passive"))
      (node (ref "U12") (pin "P$1_TIP") (pinfunction "TIP_P$1_TIP") (pintype "passive"))
      (node (ref "U8") (pin "10") (pinfunction "+IN_10") (pintype "input"))
    )
    (net (code "68") (name "Net-(U13-TIP)") (class "Default")
      (node (ref "R42") (pin "1") (pinfunction "1_1") (pintype "passive"))
      (node (ref "U13") (pin "P$1_TIP") (pinfunction "TIP_P$1_TIP") (pintype "passive"))
    )
    (net (code "69") (name "Net-(U14-TIP)") (class "Default")
      (node (ref "R43") (pin "1") (pinfunction "1_1") (pintype "passive"))
      (node (ref "U14") (pin "P$1_TIP") (pinfunction "TIP_P$1_TIP") (pintype "passive"))
    )
    (net (code "70") (name "Net-(U15-TIP)") (class "Default")
      (node (ref "R44") (pin "1") (pinfunction "1_1") (pintype "passive"))
      (node (ref "U15") (pin "P$1_TIP") (pinfunction "TIP_P$1_TIP") (pintype "passive"))
    )
    (net (code "71") (name "Net-(U16-TIP)") (class "Default")
      (node (ref "R45") (pin "1") (pinfunction "1_1") (pintype "passive"))
      (node (ref "U16") (pin "P$1_TIP") (pinfunction "TIP_P$1_TIP") (pintype "passive"))
    )
    (net (code "72") (name "Net-(U17A--IN)") (class "Default")
      (node (ref "R50") (pin "2") (pinfunction "2_2") (pintype "passive"))
      (node (ref "R58") (pin "1") (pinfunction "1_1") (pintype "passive"))
      (node (ref "U17") (pin "2") (pinfunction "-IN_2") (pintype "input"))
    )
    (net (code "73") (name "Net-(U17A-OUT)") (class "Default")
      (node (ref "R58") (pin "2") (pinfunction "2_2") (pintype "passive"))
      (node (ref "R66") (pin "1") (pinfunction "1_1") (pintype "passive"))
      (node (ref "U17") (pin "1") (pinfunction "OUT_1") (pintype "output"))
    )
    (net (code "74") (name "Net-(U17B--IN)") (class "Default")
      (node (ref "R47") (pin "2") (pinfunction "2_2") (pintype "passive"))
      (node (ref "R55") (pin "1") (pinfunction "1_1") (pintype "passive"))
      (node (ref "U17") (pin "6") (pinfunction "-IN_6") (pintype "input"))
    )
    (net (code "75") (name "Net-(U17B-OUT)") (class "Default")
      (node (ref "R55") (pin "2") (pinfunction "2_2") (pintype "passive"))
      (node (ref "R62") (pin "1") (pinfunction "1_1") (pintype "passive"))
      (node (ref "U17") (pin "7") (pinfunction "OUT_7") (pintype "output"))
    )
    (net (code "76") (name "Net-(U17C-+IN)") (class "Default")
      (node (ref "R72") (pin "2") (pinfunction "2_2") (pintype "passive"))
      (node (ref "R79") (pin "2") (pinfunction "2_2") (pintype "passive"))
      (node (ref "U17") (pin "10") (pinfunction "+IN_10") (pintype "input"))
      (node (ref "U22") (pin "P$1_TIP") (pinfunction "TIP_P$1_TIP") (pintype "passive"))
    )
    (net (code "77") (name "Net-(U17C--IN)") (class "Default")
      (node (ref "LED6") (pin "A") (pinfunction "A_A") (pintype "passive"))
      (node (ref "R83") (pin "2") (pinfunction "2_2") (pintype "passive"))
      (node (ref "U17") (pin "9") (pinfunction "-IN_9") (pintype "input"))
    )
    (net (code "78") (name "Net-(U17D-+IN)") (class "Default")
      (node (ref "R70") (pin "2") (pinfunction "2_2") (pintype "passive"))
      (node (ref "R78") (pin "2") (pinfunction "2_2") (pintype "passive"))
      (node (ref "U17") (pin "12") (pinfunction "+IN_12") (pintype "input"))
      (node (ref "U21") (pin "P$1_TIP") (pinfunction "TIP_P$1_TIP") (pintype "passive"))
    )
    (net (code "79") (name "Net-(U17D--IN)") (class "Default")
      (node (ref "LED5") (pin "A") (pinfunction "A_A") (pintype "passive"))
      (node (ref "R82") (pin "2") (pinfunction "2_2") (pintype "passive"))
      (node (ref "U17") (pin "13") (pinfunction "-IN_13") (pintype "input"))
    )
    (net (code "80") (name "Net-(U18A--IN)") (class "Default")
      (node (ref "R48") (pin "2") (pinfunction "2_2") (pintype "passive"))
      (node (ref "R56") (pin "1") (pinfunction "1_1") (pintype "passive"))
      (node (ref "U18") (pin "2") (pinfunction "-IN_2") (pintype "input"))
    )
    (net (code "81") (name "Net-(U18A-OUT)") (class "Default")
      (node (ref "R56") (pin "2") (pinfunction "2_2") (pintype "passive"))
      (node (ref "R63") (pin "1") (pinfunction "1_1") (pintype "passive"))
      (node (ref "U18") (pin "1") (pinfunction "OUT_1") (pintype "output"))
    )
    (net (code "82") (name "Net-(U18B--IN)") (class "Default")
      (node (ref "U18") (pin "6") (pinfunction "-IN_6") (pintype "input"))
      (node (ref "U18") (pin "7") (pinfunction "OUT_7") (pintype "output"))
    )
    (net (code "83") (name "Net-(U18C-+IN)") (class "Default")
      (node (ref "R76") (pin "2") (pinfunction "2_2") (pintype "passive"))
      (node (ref "R81") (pin "2") (pinfunction "2_2") (pintype "passive"))
      (node (ref "U18") (pin "10") (pinfunction "+IN_10") (pintype "input"))
      (node (ref "U24") (pin "P$1_TIP") (pinfunction "TIP_P$1_TIP") (pintype "passive"))
    )
    (net (code "84") (name "Net-(U18C--IN)") (class "Default")
      (node (ref "LED8") (pin "A") (pinfunction "A_A") (pintype "passive"))
      (node (ref "R85") (pin "2") (pinfunction "2_2") (pintype "passive"))
      (node (ref "U18") (pin "9") (pinfunction "-IN_9") (pintype "input"))
    )
    (net (code "85") (name "Net-(U18D-+IN)") (class "Default")
      (node (ref "R74") (pin "2") (pinfunction "2_2") (pintype "passive"))
      (node (ref "R80") (pin "2") (pinfunction "2_2") (pintype "passive"))
      (node (ref "U18") (pin "12") (pinfunction "+IN_12") (pintype "input"))
      (node (ref "U23") (pin "P$1_TIP") (pinfunction "TIP_P$1_TIP") (pintype "passive"))
    )
    (net (code "86") (name "Net-(U18D--IN)") (class "Default")
      (node (ref "LED7") (pin "A") (pinfunction "A_A") (pintype "passive"))
      (node (ref "R84") (pin "2") (pinfunction "2_2") (pintype "passive"))
      (node (ref "U18") (pin "13") (pinfunction "-IN_13") (pintype "input"))
    )
    (net (code "87") (name "Net-(U19A-OUT)") (class "Default")
      (node (ref "R57") (pin "2") (pinfunction "2_2") (pintype "passive"))
      (node (ref "R65") (pin "1") (pinfunction "1_1") (pintype "passive"))
      (node (ref "U19") (pin "1") (pinfunction "OUT_1") (pintype "output"))
    )
    (net (code "88") (name "Net-(U19B-OUT)") (class "Default")
      (node (ref "R59") (pin "2") (pinfunction "2_2") (pintype "passive"))
      (node (ref "R67") (pin "1") (pinfunction "1_1") (pintype "passive"))
      (node (ref "U19") (pin "7") (pinfunction "OUT_7") (pintype "output"))
    )
    (net (code "89") (name "Net-(U19C-OUT)") (class "Default")
      (node (ref "C30") (pin "2") (pinfunction "2_2") (pintype "passive"))
      (node (ref "R79") (pin "1") (pinfunction "1_1") (pintype "passive"))
      (node (ref "U19") (pin "8") (pinfunction "OUT_8") (pintype "output"))
    )
    (net (code "90") (name "Net-(U19D-OUT)") (class "Default")
      (node (ref "C29") (pin "2") (pinfunction "2_2") (pintype "passive"))
      (node (ref "R78") (pin "1") (pinfunction "1_1") (pintype "passive"))
      (node (ref "U19") (pin "14") (pinfunction "OUT_14") (pintype "output"))
    )
    (net (code "91") (name "Net-(U20A-OUT)") (class "Default")
      (node (ref "R60") (pin "2") (pinfunction "2_2") (pintype "passive"))
      (node (ref "R68") (pin "1") (pinfunction "1_1") (pintype "passive"))
      (node (ref "U20") (pin "1") (pinfunction "OUT_1") (pintype "output"))
    )
    (net (code "92") (name "Net-(U20B-OUT)") (class "Default")
      (node (ref "R61") (pin "2") (pinfunction "2_2") (pintype "passive"))
      (node (ref "R69") (pin "1") (pinfunction "1_1") (pintype "passive"))
      (node (ref "U20") (pin "7") (pinfunction "OUT_7") (pintype "output"))
    )
    (net (code "93") (name "Net-(U20C-OUT)") (class "Default")
      (node (ref "C32") (pin "2") (pinfunction "2_2") (pintype "passive"))
      (node (ref "R81") (pin "1") (pinfunction "1_1") (pintype "passive"))
      (node (ref "U20") (pin "8") (pinfunction "OUT_8") (pintype "output"))
    )
    (net (code "94") (name "Net-(U20D-OUT)") (class "Default")
      (node (ref "C31") (pin "2") (pinfunction "2_2") (pintype "passive"))
      (node (ref "R80") (pin "1") (pinfunction "1_1") (pintype "passive"))
      (node (ref "U20") (pin "14") (pinfunction "OUT_14") (pintype "output"))
    )
    (net (code "95") (name "Net-(U21-SWITCH)") (class "Default")
      (node (ref "R50") (pin "1") (pinfunction "1_1") (pintype "passive"))
      (node (ref "U21") (pin "P$2_SWITCH") (pinfunction "SWITCH_P$2_SWITCH") (pintype "passive"))
    )
    (net (code "96") (name "Net-(U22-SWITCH)") (class "Default")
      (node (ref "R47") (pin "1") (pinfunction "1_1") (pintype "passive"))
      (node (ref "U22") (pin "P$2_SWITCH") (pinfunction "SWITCH_P$2_SWITCH") (pintype "passive"))
    )
    (net (code "97") (name "Net-(U23-SWITCH)") (class "Default")
      (node (ref "R48") (pin "1") (pinfunction "1_1") (pintype "passive"))
      (node (ref "U23") (pin "P$2_SWITCH") (pinfunction "SWITCH_P$2_SWITCH") (pintype "passive"))
    )
    (net (code "98") (name "OUT_4_NORMAL") (class "Default")
      (node (ref "R46") (pin "1") (pinfunction "1_1") (pintype "passive"))
      (node (ref "U12") (pin "P$2_SWITCH") (pinfunction "SWITCH_P$2_SWITCH") (pintype "passive"))
    )
    (net (code "99") (name "VCC") (class "Default")
      (node (ref "C12") (pin "+") (pinfunction "+_+") (pintype "passive"))
      (node (ref "C13") (pin "1") (pinfunction "1_1") (pintype "passive"))
      (node (ref "C14") (pin "1") (pinfunction "1_1") (pintype "passive"))
      (node (ref "C15") (pin "1") (pinfunction "1_1") (pintype "passive"))
      (node (ref "C16") (pin "1") (pinfunction "1_1") (pintype "passive"))
      (node (ref "C17") (pin "1") (pinfunction "1_1") (pintype "passive"))
      (node (ref "C18") (pin "1") (pinfunction "1_1") (pintype "passive"))
      (node (ref "C19") (pin "1") (pinfunction "1_1") (pintype "passive"))
      (node (ref "C20") (pin "1") (pinfunction "1_1") (pintype "passive"))
      (node (ref "C21") (pin "1") (pinfunction "1_1") (pintype "passive"))
      (node (ref "C23") (pin "1") (pinfunction "1_1") (pintype "passive"))
      (node (ref "D2") (pin "C") (pinfunction "C_C") (pintype "passive"))
      (node (ref "IC1") (pin "3") (pinfunction "VI_3") (pintype "input"))
      (node (ref "U17") (pin "4") (pinfunction "V+_4") (pintype "power_in"))
      (node (ref "U18") (pin "4") (pinfunction "V+_4") (pintype "power_in"))
      (node (ref "U19") (pin "4") (pinfunction "V+_4") (pintype "power_in"))
      (node (ref "U20") (pin "4") (pinfunction "V+_4") (pintype "power_in"))
      (node (ref "U5") (pin "4") (pinfunction "V+_4") (pintype "power_in"))
      (node (ref "U6") (pin "4") (pinfunction "V+_4") (pintype "power_in"))
      (node (ref "U7") (pin "4") (pinfunction "V+_4") (pintype "power_in"))
      (node (ref "U8") (pin "4") (pinfunction "V+_4") (pintype "power_in"))
    )
    (net (code "100") (name "VEE") (class "Default")
      (node (ref "C1") (pin "-") (pinfunction "-_-") (pintype "passive"))
      (node (ref "C10") (pin "2") (pinfunction "2_2") (pintype "passive"))
      (node (ref "C2") (pin "2") (pinfunction "2_2") (pintype "passive"))
      (node (ref "C3") (pin "2") (pinfunction "2_2") (pintype "passive"))
      (node (ref "C4") (pin "2") (pinfunction "2_2") (pintype "passive"))
      (node (ref "C5") (pin "2") (pinfunction "2_2") (pintype "passive"))
      (node (ref "C6") (pin "2") (pinfunction "2_2") (pintype "passive"))
      (node (ref "C7") (pin "2") (pinfunction "2_2") (pintype "passive"))
      (node (ref "C8") (pin "2") (pinfunction "2_2") (pintype "passive"))
      (node (ref "C9") (pin "2") (pinfunction "2_2") (pintype "passive"))
      (node (ref "D1") (pin "A") (pinfunction "A_A") (pintype "passive"))
      (node (ref "U17") (pin "11") (pinfunction "V-_11") (pintype "power_in"))
      (node (ref "U18") (pin "11") (pinfunction "V-_11") (pintype "power_in"))
      (node (ref "U19") (pin "11") (pinfunction "V-_11") (pintype "power_in"))
      (node (ref "U20") (pin "11") (pinfunction "V-_11") (pintype "power_in"))
      (node (ref "U5") (pin "11") (pinfunction "V-_11") (pintype "power_in"))
      (node (ref "U6") (pin "11") (pinfunction "V-_11") (pintype "power_in"))
      (node (ref "U7") (pin "11") (pinfunction "V-_11") (pintype "power_in"))
      (node (ref "U8") (pin "11") (pinfunction "V-_11") (pintype "power_in"))
    )
    (net (code "101") (name "unconnected-(U24-SWITCH-PadP$2_SWITCH)") (class "Default")
      (node (ref "U24") (pin "P$2_SWITCH") (pinfunction "SWITCH_P$2_SWITCH") (pintype "passive"))
    )
  )
)
